# Pulvertech_basic.net
KiCad netlist of a schematic drawn in EAGLE
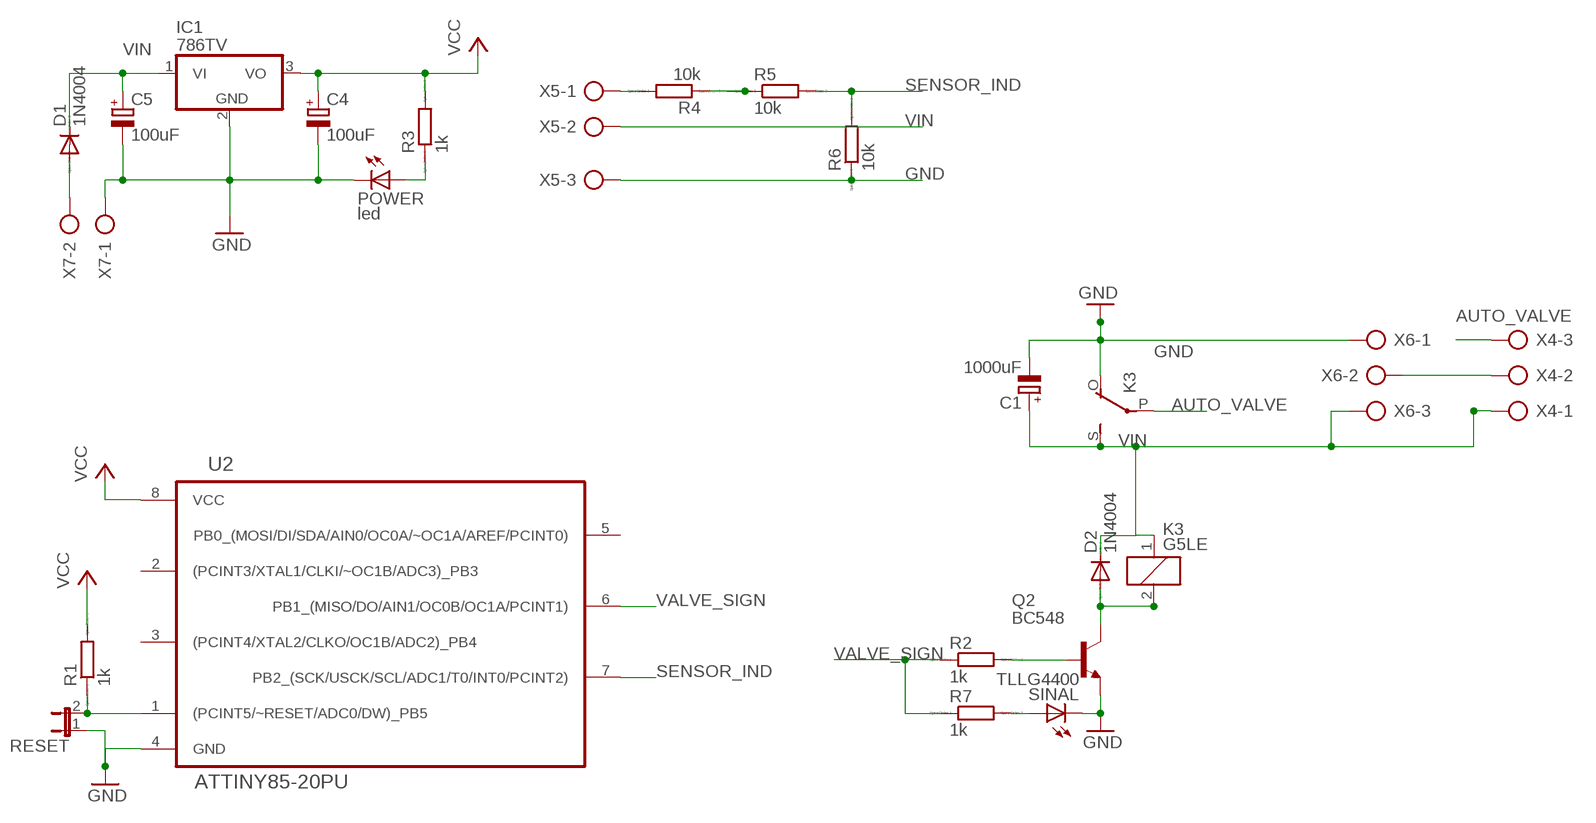
[diagram p0: schematic, sheet 1]

(export (version "E")
  (design (tool "Eeschema 10.0.6"))
  (components
    (comp (ref "C1")
      (value "1000uF")
      (footprint "eagle-import:E5-10,5")
      (libsource (lib "eagle-import") (part "CPOL-EUE5-10.5"))
    )
    (comp (ref "C4")
      (value "100uF")
      (footprint "eagle-import:E2,5-5")
      (libsource (lib "eagle-import") (part "CPOL-EUE2.5-5"))
    )
    (comp (ref "C5")
      (value "100uF")
      (footprint "eagle-import:E2,5-5")
      (libsource (lib "eagle-import") (part "CPOL-EUE2.5-5"))
    )
    (comp (ref "D1")
      (value "1N4004")
      (footprint "eagle-import:DO41-10")
      (libsource (lib "eagle-import") (part "1N4004"))
    )
    (comp (ref "D2")
      (value "1N4004")
      (footprint "eagle-import:DO41-10")
      (libsource (lib "eagle-import") (part "1N4004"))
    )
    (comp (ref "IC1")
      (value "786TV")
      (footprint "eagle-import:TO220V")
      (libsource (lib "eagle-import") (part "78TV6"))
    )
    (comp (ref "K3")
      (value "G5LE")
      (footprint "eagle-import:G5LE")
      (libsource (lib "eagle-import") (part "G5LE"))
    )
    (comp (ref "POWER")
      (value "led")
      (footprint "eagle-import:LED3MM")
      (libsource (lib "eagle-import") (part "LED3MM"))
    )
    (comp (ref "Q2")
      (value "BC548")
      (footprint "eagle-import:TO92-EBC")
      (libsource (lib "eagle-import") (part "BC548"))
    )
    (comp (ref "R1")
      (value "1k")
      (footprint "eagle-import:0204_7")
      (libsource (lib "eagle-import") (part "R0204/7"))
    )
    (comp (ref "R2")
      (value "1k")
      (footprint "eagle-import:0204_7")
      (libsource (lib "eagle-import") (part "R0204/7"))
    )
    (comp (ref "R3")
      (value "1k")
      (footprint "eagle-import:0204_7")
      (libsource (lib "eagle-import") (part "R0204/7"))
    )
    (comp (ref "R4")
      (value "10k")
      (footprint "eagle-import:0204_7")
      (libsource (lib "eagle-import") (part "R0204/7"))
    )
    (comp (ref "R5")
      (value "10k")
      (footprint "eagle-import:0204_7")
      (libsource (lib "eagle-import") (part "R0204/7"))
    )
    (comp (ref "R6")
      (value "10k")
      (footprint "eagle-import:0204_7")
      (libsource (lib "eagle-import") (part "R0204/7"))
    )
    (comp (ref "R7")
      (value "1k")
      (footprint "eagle-import:0204_7")
      (libsource (lib "eagle-import") (part "R0204/7"))
    )
    (comp (ref "RESET")
      (value "JP1E")
      (footprint "eagle-import:JP1")
      (libsource (lib "eagle-import") (part "JP1E"))
    )
    (comp (ref "SINAL")
      (value "TLLG4400")
      (footprint "eagle-import:LED3MM")
      (fields (field (name "MF") "VISHAY SEMICONDUCTOR"))
      (libsource (lib "eagle-import") (part "TLLG4400"))
    )
    (comp (ref "U2")
      (value "ATTINY85-20PU")
      (footprint "eagle-import:DIP254P762X533-8")
      (libsource (lib "eagle-import") (part "ATTINY85-20PU"))
    )
    (comp (ref "X4")
      (value "AK500/3")
      (footprint "eagle-import:AK500_3")
      (libsource (lib "eagle-import") (part "AK500/3"))
    )
    (comp (ref "X5")
      (value "AK500/3")
      (footprint "eagle-import:AK500_3")
      (libsource (lib "eagle-import") (part "AK500/3"))
    )
    (comp (ref "X6")
      (value "AK500/3")
      (footprint "eagle-import:AK500_3")
      (libsource (lib "eagle-import") (part "AK500/3"))
    )
    (comp (ref "X7")
      (value "AK500/2")
      (footprint "eagle-import:AK500_2")
      (libsource (lib "eagle-import") (part "AK500/2"))
    )
  )
  (nets
    (net (code "1") (name "/AUTO_VALVE") (class "Default")
      (node (ref "K3") (pin "P") (pinfunction "P_P") (pintype "passive"))
      (node (ref "X4") (pin "3") (pinfunction "KL_3") (pintype "passive"))
    )
    (net (code "2") (name "/SENSOR_IND") (class "Default")
      (node (ref "R5") (pin "2") (pinfunction "2_2") (pintype "passive"))
      (node (ref "R6") (pin "2") (pinfunction "2_2") (pintype "passive"))
      (node (ref "U2") (pin "7") (pinfunction "PB2_(SCK/USCK/SCL/ADC1/T0/INT0/PCINT2)_7") (pintype "bidirectional"))
    )
    (net (code "3") (name "/VALVE_SIGN") (class "Default")
      (node (ref "R2") (pin "1") (pinfunction "1_1") (pintype "passive"))
      (node (ref "R7") (pin "1") (pinfunction "1_1") (pintype "passive"))
      (node (ref "U2") (pin "6") (pinfunction "PB1_(MISO/DO/AIN1/OC0B/OC1A/PCINT1)_6") (pintype "bidirectional"))
    )
    (net (code "4") (name "/VIN") (class "Default")
      (node (ref "C1") (pin "+") (pinfunction "+_+") (pintype "passive"))
      (node (ref "C5") (pin "+") (pinfunction "+_+") (pintype "passive"))
      (node (ref "D1") (pin "C") (pinfunction "C_C") (pintype "passive"))
      (node (ref "D2") (pin "C") (pinfunction "C_C") (pintype "passive"))
      (node (ref "IC1") (pin "1") (pinfunction "VI_1") (pintype "input"))
      (node (ref "K3") (pin "1") (pinfunction "1_1") (pintype "passive"))
      (node (ref "K3") (pin "S") (pinfunction "S_S") (pintype "passive"))
      (node (ref "X4") (pin "1") (pinfunction "KL_1") (pintype "passive"))
      (node (ref "X5") (pin "2") (pinfunction "KL_2") (pintype "passive"))
      (node (ref "X6") (pin "3") (pinfunction "KL_3") (pintype "passive"))
    )
    (net (code "5") (name "GND") (class "Default")
      (node (ref "C1") (pin "-") (pinfunction "-_-") (pintype "passive"))
      (node (ref "C4") (pin "-") (pinfunction "-_-") (pintype "passive"))
      (node (ref "C5") (pin "-") (pinfunction "-_-") (pintype "passive"))
      (node (ref "IC1") (pin "2") (pinfunction "GND_2") (pintype "passive"))
      (node (ref "K3") (pin "O") (pinfunction "O_O") (pintype "passive"))
      (node (ref "POWER") (pin "K") (pinfunction "C_K") (pintype "passive"))
      (node (ref "Q2") (pin "E") (pinfunction "E_E") (pintype "passive"))
      (node (ref "R6") (pin "1") (pinfunction "1_1") (pintype "passive"))
      (node (ref "RESET") (pin "1") (pinfunction "1_1") (pintype "passive"))
      (node (ref "SINAL") (pin "K") (pinfunction "C_K") (pintype "passive"))
      (node (ref "U2") (pin "4") (pinfunction "GND_4") (pintype "passive"))
      (node (ref "X5") (pin "3") (pinfunction "KL_3") (pintype "passive"))
      (node (ref "X6") (pin "1") (pinfunction "KL_1") (pintype "passive"))
      (node (ref "X7") (pin "1") (pinfunction "KL_1") (pintype "passive"))
    )
    (net (code "6") (name "Net-(D2-PadA)") (class "Default")
      (node (ref "D2") (pin "A") (pinfunction "A_A") (pintype "passive"))
      (node (ref "K3") (pin "2") (pinfunction "2_2") (pintype "passive"))
      (node (ref "Q2") (pin "C") (pinfunction "C_C") (pintype "passive"))
    )
    (net (code "7") (name "Net-(POWER-PadA)") (class "Default")
      (node (ref "POWER") (pin "A") (pinfunction "A_A") (pintype "passive"))
      (node (ref "R3") (pin "1") (pinfunction "1_1") (pintype "passive"))
    )
    (net (code "8") (name "Net-(Q2-PadB)") (class "Default")
      (node (ref "Q2") (pin "B") (pinfunction "B_B") (pintype "passive"))
      (node (ref "R2") (pin "2") (pinfunction "2_2") (pintype "passive"))
    )
    (net (code "9") (name "Net-(R4-Pad1)") (class "Default")
      (node (ref "R4") (pin "1") (pinfunction "1_1") (pintype "passive"))
      (node (ref "R5") (pin "1") (pinfunction "1_1") (pintype "passive"))
    )
    (net (code "10") (name "Net-(R7-Pad2)") (class "Default")
      (node (ref "R7") (pin "2") (pinfunction "2_2") (pintype "passive"))
      (node (ref "SINAL") (pin "A") (pinfunction "A_A") (pintype "passive"))
    )
    (net (code "11") (name "Net-(U2-(PCINT5{slash}~{RESET{slash}ADC0{slash}DW})_PB5)") (class "Default")
      (node (ref "R1") (pin "1") (pinfunction "1_1") (pintype "passive"))
      (node (ref "RESET") (pin "2") (pinfunction "2_2") (pintype "passive"))
      (node (ref "U2") (pin "1") (pinfunction "(PCINT5/~{RESET/ADC0/DW})_PB5_1") (pintype "bidirectional"))
    )
    (net (code "12") (name "Net-(X4B-KL)") (class "Default")
      (node (ref "X4") (pin "2") (pinfunction "KL_2") (pintype "passive"))
      (node (ref "X6") (pin "2") (pinfunction "KL_2") (pintype "passive"))
    )
    (net (code "13") (name "Net-(X5A-KL)") (class "Default")
      (node (ref "R4") (pin "2") (pinfunction "2_2") (pintype "passive"))
      (node (ref "X5") (pin "1") (pinfunction "KL_1") (pintype "passive"))
    )
    (net (code "14") (name "Net-(X7B-KL)") (class "Default")
      (node (ref "D1") (pin "A") (pinfunction "A_A") (pintype "passive"))
      (node (ref "X7") (pin "2") (pinfunction "KL_2") (pintype "passive"))
    )
    (net (code "15") (name "VCC") (class "Default")
      (node (ref "C4") (pin "+") (pinfunction "+_+") (pintype "passive"))
      (node (ref "IC1") (pin "3") (pinfunction "VO_3") (pintype "passive"))
      (node (ref "R1") (pin "2") (pinfunction "2_2") (pintype "passive"))
      (node (ref "R3") (pin "2") (pinfunction "2_2") (pintype "passive"))
      (node (ref "U2") (pin "8") (pinfunction "VCC_8") (pintype "power_in"))
    )
    (net (code "16") (name "unconnected-(U2-(PCINT3{slash}XTAL1{slash}CLKI{slash}~{OC1B{slash}ADC3})_PB3-Pad2)") (class "Default")
      (node (ref "U2") (pin "2") (pinfunction "(PCINT3/XTAL1/CLKI/~{OC1B/ADC3})_PB3_2") (pintype "bidirectional"))
    )
    (net (code "17") (name "unconnected-(U2-(PCINT4{slash}XTAL2{slash}CLKO{slash}OC1B{slash}ADC2)_PB4-Pad3)") (class "Default")
      (node (ref "U2") (pin "3") (pinfunction "(PCINT4/XTAL2/CLKO/OC1B/ADC2)_PB4_3") (pintype "bidirectional"))
    )
    (net (code "18") (name "unconnected-(U2-PB0_(MOSI{slash}DI{slash}SDA{slash}AIN0{slash}OC0A{slash}~{OC1A{slash}AREF{slash}PCINT0})-Pad5)") (class "Default")
      (node (ref "U2") (pin "5") (pinfunction "PB0_(MOSI/DI/SDA/AIN0/OC0A/~{OC1A/AREF/PCINT0})_5") (pintype "bidirectional"))
    )
  )
)
